# Sheet1.net
KiCad netlist of a schematic drawn in Altium Designer
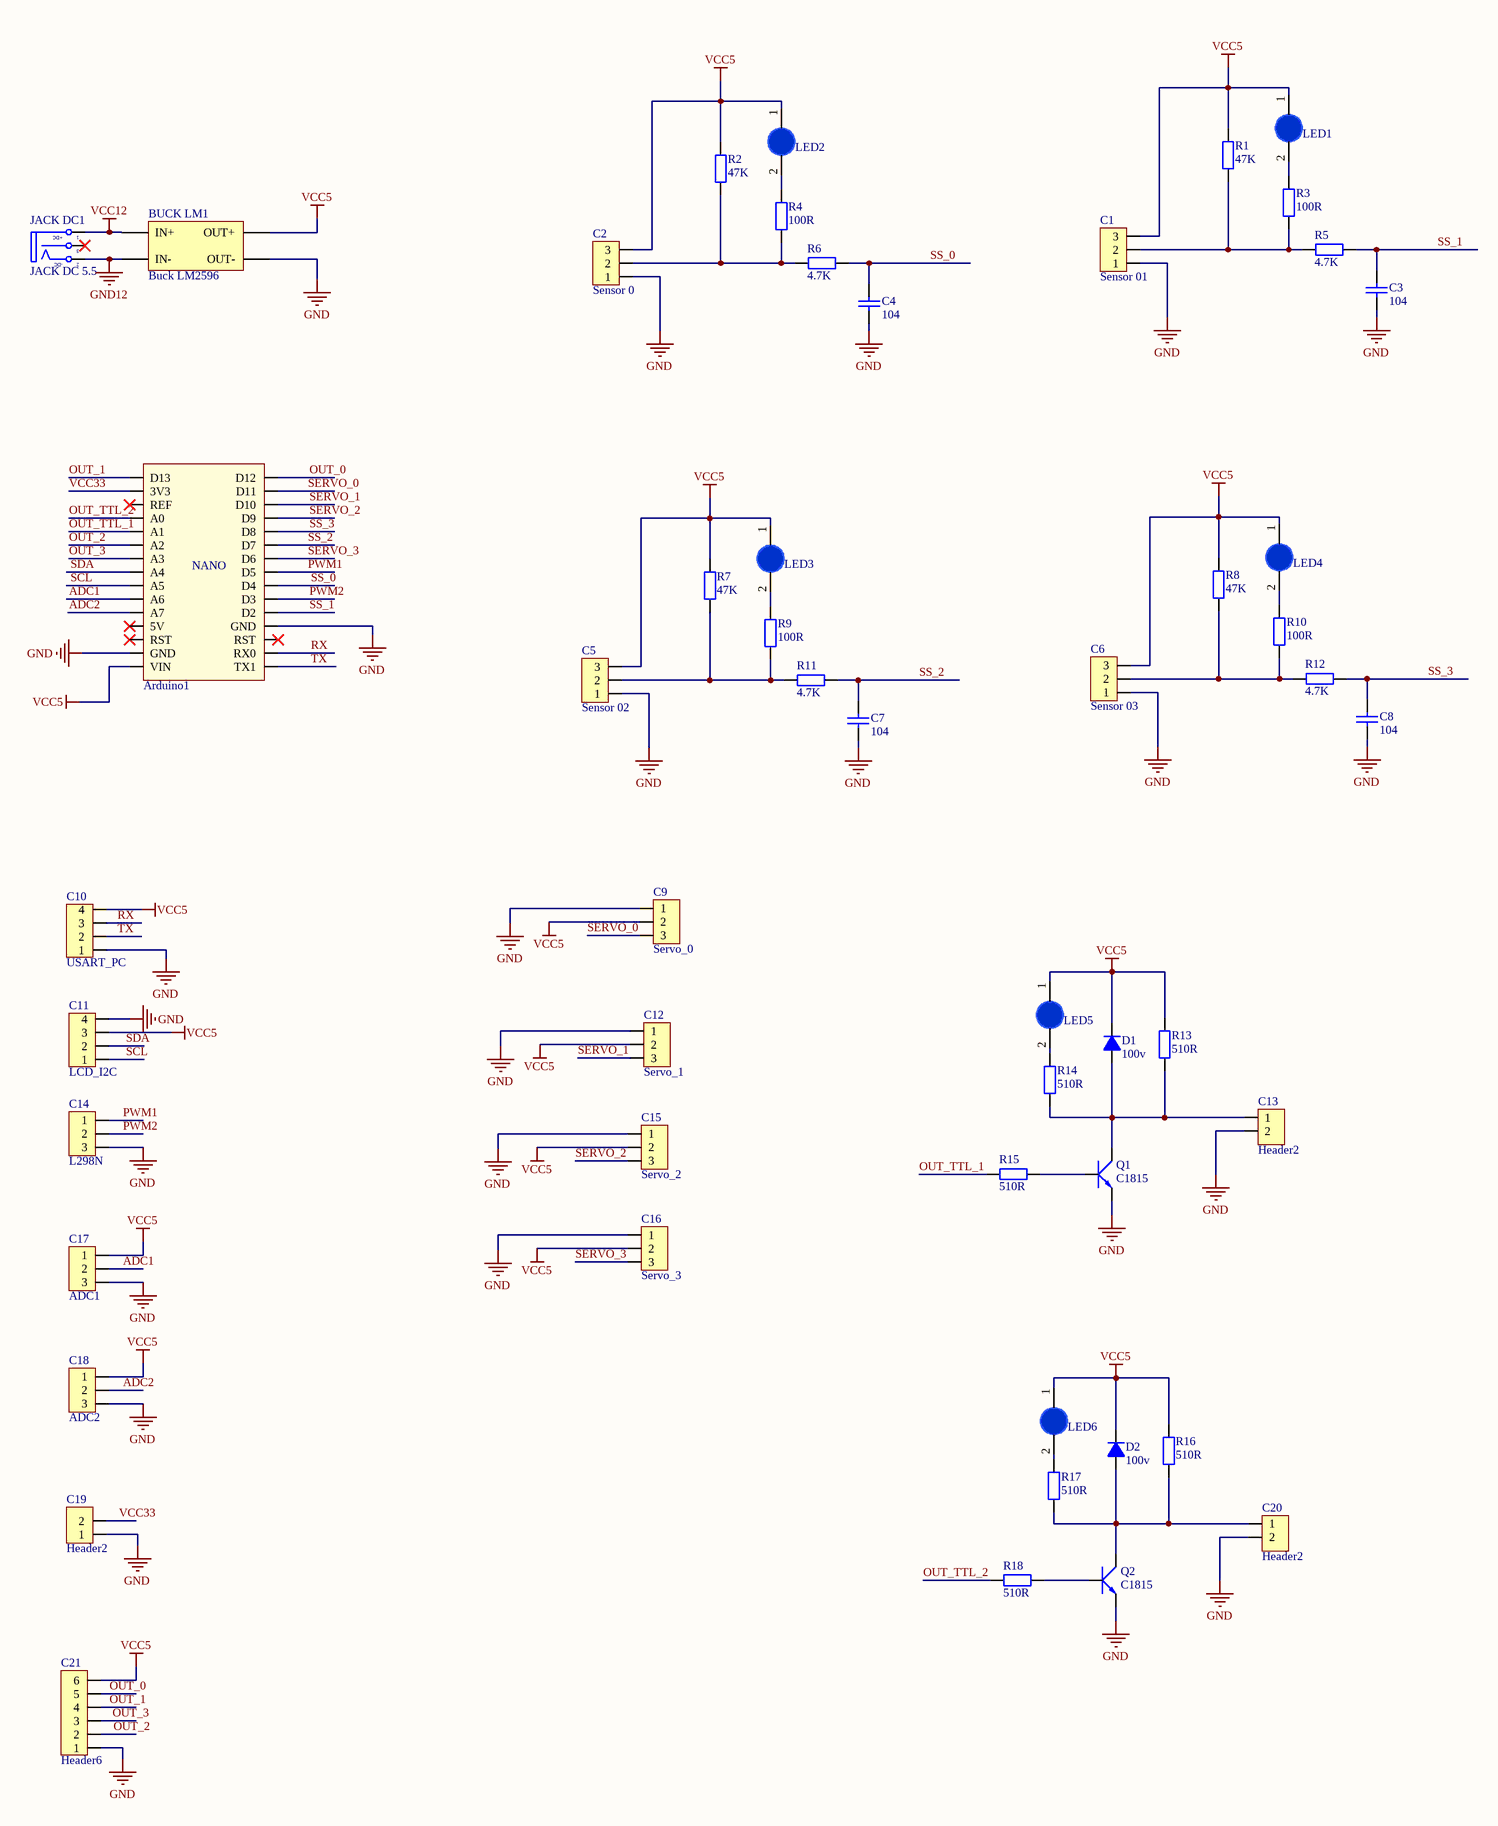
[diagram p0: Sheet1.SchDoc]

(export (version "E")
  (design (tool "Eeschema 10.0.6"))
  (components
    (comp (ref "Arduino1")
      (value "Arduino Nano")
      (footprint "Arduino Nano")
      (description "Arduino NANO")
      (libsource (lib "myLib_v1") (part "Arduino Nano"))
    )
    (comp (ref "BUCK LM1")
      (value "Buck LM2596")
      (footprint "BUCK LM2596")
      (libsource (lib "myLib_v1") (part "Buck LM2596"))
    )
    (comp (ref "C1")
      (value "Sensor 01")
      (footprint "Header3")
      (description "Header IDC, 3 x 1 Pin Vertical 2.54mm Pitch (Non-Boxed, Male)")
      (fields
        (field (name "MANUFACTURER") "Würth Elektronik eiSos GmbH")
        (field (name "PARTNO") "613002143121")
        (field (name "CREATED BY") "Karrer Zheng")
      )
      (libsource (lib "") (part "Header3_1"))
    )
    (comp (ref "C2")
      (value "Sensor 0")
      (footprint "Header3")
      (description "Header IDC, 3 x 1 Pin Vertical 2.54mm Pitch (Non-Boxed, Male)")
      (fields
        (field (name "MANUFACTURER") "Würth Elektronik eiSos GmbH")
        (field (name "PARTNO") "613002143121")
        (field (name "CREATED BY") "Karrer Zheng")
      )
      (libsource (lib "") (part "Header3_1"))
    )
    (comp (ref "C3")
      (value "104")
      (footprint "tu gom")
      (description "Cắm")
      (libsource (lib "Altium_Lib_by_KhueNguyenCreator") (part "Tu gom 104 50V"))
    )
    (comp (ref "C4")
      (value "104")
      (footprint "tu gom")
      (description "Cắm")
      (libsource (lib "Altium_Lib_by_KhueNguyenCreator") (part "Tu gom 104 50V"))
    )
    (comp (ref "C5")
      (value "Sensor 02")
      (footprint "Header3")
      (description "Header IDC, 3 x 1 Pin Vertical 2.54mm Pitch (Non-Boxed, Male)")
      (fields
        (field (name "MANUFACTURER") "Würth Elektronik eiSos GmbH")
        (field (name "PARTNO") "613002143121")
        (field (name "CREATED BY") "Karrer Zheng")
      )
      (libsource (lib "") (part "Header3_1"))
    )
    (comp (ref "C6")
      (value "Sensor 03")
      (footprint "Header3")
      (description "Header IDC, 3 x 1 Pin Vertical 2.54mm Pitch (Non-Boxed, Male)")
      (fields
        (field (name "MANUFACTURER") "Würth Elektronik eiSos GmbH")
        (field (name "PARTNO") "613002143121")
        (field (name "CREATED BY") "Karrer Zheng")
      )
      (libsource (lib "") (part "Header3_1"))
    )
    (comp (ref "C7")
      (value "104")
      (footprint "tu gom")
      (description "Cắm")
      (libsource (lib "Altium_Lib_by_KhueNguyenCreator") (part "Tu gom 104 50V"))
    )
    (comp (ref "C8")
      (value "104")
      (footprint "tu gom")
      (description "Cắm")
      (libsource (lib "Altium_Lib_by_KhueNguyenCreator") (part "Tu gom 104 50V"))
    )
    (comp (ref "C9")
      (value "Servo_0")
      (footprint "Header3")
      (description "Header IDC, 3 x 1 Pin Vertical 2.54mm Pitch (Non-Boxed, Male)")
      (fields
        (field (name "MANUFACTURER") "Würth Elektronik eiSos GmbH")
        (field (name "PARTNO") "613002143121")
        (field (name "CREATED BY") "Karrer Zheng")
      )
      (libsource (lib "") (part "Header3_2"))
    )
    (comp (ref "C10")
      (value "USART_PC")
      (footprint "Header4")
      (description "Header IDC, 4 x 1 Pin Vertical 2.54mm Pitch (Non-Boxed, Male)")
      (fields
        (field (name "MANUFACTURER") "Würth Elektronik eiSos GmbH")
        (field (name "PARTNO") "613002143121")
        (field (name "CREATED BY") "Karrer Zheng")
      )
      (libsource (lib "myLib_v1") (part "Header4"))
    )
    (comp (ref "C11")
      (value "LCD_I2C")
      (footprint "Header4")
      (description "Header IDC, 4 x 1 Pin Vertical 2.54mm Pitch (Non-Boxed, Male)")
      (fields
        (field (name "MANUFACTURER") "Würth Elektronik eiSos GmbH")
        (field (name "PARTNO") "613002143121")
        (field (name "CREATED BY") "Karrer Zheng")
      )
      (libsource (lib "myLib_v1") (part "Header4"))
    )
    (comp (ref "C12")
      (value "Servo_1")
      (footprint "Header3")
      (description "Header IDC, 3 x 1 Pin Vertical 2.54mm Pitch (Non-Boxed, Male)")
      (fields
        (field (name "MANUFACTURER") "Würth Elektronik eiSos GmbH")
        (field (name "PARTNO") "613002143121")
        (field (name "CREATED BY") "Karrer Zheng")
      )
      (libsource (lib "") (part "Header3_2"))
    )
    (comp (ref "C13")
      (value "Header2")
      (footprint "Header2")
      (description "Header IDC, 2 x 1 Pin Vertical 2.54mm Pitch (Non-Boxed, Male)")
      (fields
        (field (name "MANUFACTURER") "Würth Elektronik eiSos GmbH")
        (field (name "PARTNO") "613002143121")
        (field (name "CREATED BY") "Karrer Zheng")
      )
      (libsource (lib "myLib_v1") (part "Header2"))
    )
    (comp (ref "C14")
      (value "L298N")
      (footprint "Header3")
      (description "Header IDC, 3 x 1 Pin Vertical 2.54mm Pitch (Non-Boxed, Male)")
      (fields
        (field (name "MANUFACTURER") "Würth Elektronik eiSos GmbH")
        (field (name "PARTNO") "613002143121")
        (field (name "CREATED BY") "Karrer Zheng")
      )
      (libsource (lib "myLib_v1") (part "Header3"))
    )
    (comp (ref "C15")
      (value "Servo_2")
      (footprint "Header3")
      (description "Header IDC, 3 x 1 Pin Vertical 2.54mm Pitch (Non-Boxed, Male)")
      (fields
        (field (name "MANUFACTURER") "Würth Elektronik eiSos GmbH")
        (field (name "PARTNO") "613002143121")
        (field (name "CREATED BY") "Karrer Zheng")
      )
      (libsource (lib "") (part "Header3_2"))
    )
    (comp (ref "C16")
      (value "Servo_3")
      (footprint "Header3")
      (description "Header IDC, 3 x 1 Pin Vertical 2.54mm Pitch (Non-Boxed, Male)")
      (fields
        (field (name "MANUFACTURER") "Würth Elektronik eiSos GmbH")
        (field (name "PARTNO") "613002143121")
        (field (name "CREATED BY") "Karrer Zheng")
      )
      (libsource (lib "") (part "Header3_2"))
    )
    (comp (ref "C17")
      (value "ADC1")
      (footprint "Header3")
      (description "Header IDC, 3 x 1 Pin Vertical 2.54mm Pitch (Non-Boxed, Male)")
      (fields
        (field (name "MANUFACTURER") "Würth Elektronik eiSos GmbH")
        (field (name "PARTNO") "613002143121")
        (field (name "CREATED BY") "Karrer Zheng")
      )
      (libsource (lib "myLib_v1") (part "Header3"))
    )
    (comp (ref "C18")
      (value "ADC2")
      (footprint "Header3")
      (description "Header IDC, 3 x 1 Pin Vertical 2.54mm Pitch (Non-Boxed, Male)")
      (fields
        (field (name "MANUFACTURER") "Würth Elektronik eiSos GmbH")
        (field (name "PARTNO") "613002143121")
        (field (name "CREATED BY") "Karrer Zheng")
      )
      (libsource (lib "myLib_v1") (part "Header3"))
    )
    (comp (ref "C19")
      (value "Header2")
      (footprint "Header2")
      (description "Header IDC, 2 x 1 Pin Vertical 2.54mm Pitch (Non-Boxed, Male)")
      (fields
        (field (name "MANUFACTURER") "Würth Elektronik eiSos GmbH")
        (field (name "PARTNO") "613002143121")
        (field (name "CREATED BY") "Karrer Zheng")
      )
      (libsource (lib "") (part "Header2_1"))
    )
    (comp (ref "C20")
      (value "Header2")
      (footprint "Header2")
      (description "Header IDC, 2 x 1 Pin Vertical 2.54mm Pitch (Non-Boxed, Male)")
      (fields
        (field (name "MANUFACTURER") "Würth Elektronik eiSos GmbH")
        (field (name "PARTNO") "613002143121")
        (field (name "CREATED BY") "Karrer Zheng")
      )
      (libsource (lib "myLib_v1") (part "Header2"))
    )
    (comp (ref "C21")
      (value "Header6")
      (footprint "Header6")
      (description "Header IDC, 6 x 1 Pin Vertical 2.54mm Pitch (Non-Boxed, Male)")
      (fields
        (field (name "MANUFACTURER") "Würth Elektronik eiSos GmbH")
        (field (name "PARTNO") "613002143121")
        (field (name "CREATED BY") "Karrer Zheng")
      )
      (libsource (lib "myLib_v1") (part "Header6"))
    )
    (comp (ref "D1")
      (value "100v")
      (footprint "DIODE 0.5A")
      (description "Cắm")
      (libsource (lib "Altium_Lib_by_KhueNguyenCreator") (part "Diode 1N4148"))
    )
    (comp (ref "D2")
      (value "100v")
      (footprint "DIODE 0.5A")
      (description "Cắm")
      (libsource (lib "Altium_Lib_by_KhueNguyenCreator") (part "Diode 1N4148"))
    )
    (comp (ref "JACK DC1")
      (value "JACK DC 5.5")
      (footprint "JACK DC 5.5")
      (libsource (lib "Altium_Lib_by_KhueNguyenCreator") (part "JACK DC 5.5"))
    )
    (comp (ref "LED1")
      (value "LED 3mm")
      (footprint "LED-3MM-BLUE")
      (description "Cắm")
      (libsource (lib "myLib_v1") (part "LED 3mm Xanh Duong"))
    )
    (comp (ref "LED2")
      (value "LED 3mm")
      (footprint "LED-3MM-BLUE")
      (description "Cắm")
      (libsource (lib "myLib_v1") (part "LED 3mm Xanh Duong"))
    )
    (comp (ref "LED3")
      (value "LED 3mm")
      (footprint "LED-3MM-BLUE")
      (description "Cắm")
      (libsource (lib "myLib_v1") (part "LED 3mm Xanh Duong"))
    )
    (comp (ref "LED4")
      (value "LED 3mm")
      (footprint "LED-3MM-BLUE")
      (description "Cắm")
      (libsource (lib "myLib_v1") (part "LED 3mm Xanh Duong"))
    )
    (comp (ref "LED5")
      (value "LED 3mm")
      (footprint "LED-3MM-BLUE")
      (description "Cắm")
      (libsource (lib "myLib_v1") (part "LED 3mm Xanh Duong"))
    )
    (comp (ref "LED6")
      (value "LED 3mm")
      (footprint "LED-3MM-BLUE")
      (description "Cắm")
      (libsource (lib "myLib_v1") (part "LED 3mm Xanh Duong"))
    )
    (comp (ref "Q1")
      (value "C1815")
      (footprint "C1815_cam")
      (description "NPN 600mW, ECB")
      (libsource (lib "myLib_v1") (part "C1815"))
    )
    (comp (ref "Q2")
      (value "C1815")
      (footprint "C1815_cam")
      (description "NPN 600mW, ECB")
      (libsource (lib "myLib_v1") (part "C1815"))
    )
    (comp (ref "R1")
      (value "47K")
      (footprint "R1/4W")
      (description "Resistor 1/4W")
      (libsource (lib "myLib_v1") (part "R1/4W"))
    )
    (comp (ref "R2")
      (value "47K")
      (footprint "R1/4W")
      (description "Resistor 1/4W")
      (libsource (lib "myLib_v1") (part "R1/4W"))
    )
    (comp (ref "R3")
      (value "100R")
      (footprint "R1/4W")
      (description "Resistor 1/4W")
      (libsource (lib "myLib_v1") (part "R1/4W"))
    )
    (comp (ref "R4")
      (value "100R")
      (footprint "R1/4W")
      (description "Resistor 1/4W")
      (libsource (lib "myLib_v1") (part "R1/4W"))
    )
    (comp (ref "R5")
      (value "4.7K")
      (footprint "R1/4W")
      (description "Resistor 1/4W")
      (libsource (lib "myLib_v1") (part "R1/4W"))
    )
    (comp (ref "R6")
      (value "4.7K")
      (footprint "R1/4W")
      (description "Resistor 1/4W")
      (libsource (lib "myLib_v1") (part "R1/4W"))
    )
    (comp (ref "R7")
      (value "47K")
      (footprint "R1/4W")
      (description "Resistor 1/4W")
      (libsource (lib "myLib_v1") (part "R1/4W"))
    )
    (comp (ref "R8")
      (value "47K")
      (footprint "R1/4W")
      (description "Resistor 1/4W")
      (libsource (lib "myLib_v1") (part "R1/4W"))
    )
    (comp (ref "R9")
      (value "100R")
      (footprint "R1/4W")
      (description "Resistor 1/4W")
      (libsource (lib "myLib_v1") (part "R1/4W"))
    )
    (comp (ref "R10")
      (value "100R")
      (footprint "R1/4W")
      (description "Resistor 1/4W")
      (libsource (lib "myLib_v1") (part "R1/4W"))
    )
    (comp (ref "R11")
      (value "4.7K")
      (footprint "R1/4W")
      (description "Resistor 1/4W")
      (libsource (lib "myLib_v1") (part "R1/4W"))
    )
    (comp (ref "R12")
      (value "4.7K")
      (footprint "R1/4W")
      (description "Resistor 1/4W")
      (libsource (lib "myLib_v1") (part "R1/4W"))
    )
    (comp (ref "R13")
      (value "510R")
      (footprint "R1/4W")
      (description "Resistor 1/4W")
      (libsource (lib "myLib_v1") (part "R1/4W"))
    )
    (comp (ref "R14")
      (value "510R")
      (footprint "R1/4W")
      (description "Resistor 1/4W")
      (libsource (lib "myLib_v1") (part "R1/4W"))
    )
    (comp (ref "R15")
      (value "510R")
      (footprint "R1/4W")
      (description "Resistor 1/4W")
      (libsource (lib "myLib_v1") (part "R1/4W"))
    )
    (comp (ref "R16")
      (value "510R")
      (footprint "R1/4W")
      (description "Resistor 1/4W")
      (libsource (lib "myLib_v1") (part "R1/4W"))
    )
    (comp (ref "R17")
      (value "510R")
      (footprint "R1/4W")
      (description "Resistor 1/4W")
      (libsource (lib "myLib_v1") (part "R1/4W"))
    )
    (comp (ref "R18")
      (value "510R")
      (footprint "R1/4W")
      (description "Resistor 1/4W")
      (libsource (lib "myLib_v1") (part "R1/4W"))
    )
  )
  (nets
    (net (code "1") (name "/ADC1") (class "Default")
      (node (ref "Arduino1") (pin "A6") (pinfunction "A6_A6") (pintype "passive"))
      (node (ref "C17") (pin "2") (pinfunction "2_2") (pintype "passive"))
    )
    (net (code "2") (name "/ADC2") (class "Default")
      (node (ref "Arduino1") (pin "A7") (pinfunction "A7_A7") (pintype "passive"))
      (node (ref "C18") (pin "2") (pinfunction "2_2") (pintype "passive"))
    )
    (net (code "3") (name "/OUT_0") (class "Default")
      (node (ref "Arduino1") (pin "D12") (pinfunction "D12_D12") (pintype "passive"))
      (node (ref "C21") (pin "5") (pinfunction "5_5") (pintype "passive"))
    )
    (net (code "4") (name "/OUT_1") (class "Default")
      (node (ref "Arduino1") (pin "D13") (pinfunction "D13_D13") (pintype "passive"))
      (node (ref "C21") (pin "4") (pinfunction "4_4") (pintype "passive"))
    )
    (net (code "5") (name "/OUT_2") (class "Default")
      (node (ref "Arduino1") (pin "A2") (pinfunction "A2_A2") (pintype "passive"))
      (node (ref "C21") (pin "2") (pinfunction "2_2") (pintype "passive"))
    )
    (net (code "6") (name "/OUT_3") (class "Default")
      (node (ref "Arduino1") (pin "A3") (pinfunction "A3_A3") (pintype "passive"))
      (node (ref "C21") (pin "3") (pinfunction "3_3") (pintype "passive"))
    )
    (net (code "7") (name "/OUT_TTL_1") (class "Default")
      (node (ref "Arduino1") (pin "A1") (pinfunction "A1_A1") (pintype "passive"))
      (node (ref "R15") (pin "1") (pinfunction "1_1") (pintype "passive"))
    )
    (net (code "8") (name "/OUT_TTL_2") (class "Default")
      (node (ref "Arduino1") (pin "A0") (pinfunction "A0_A0") (pintype "passive"))
      (node (ref "R18") (pin "1") (pinfunction "1_1") (pintype "passive"))
    )
    (net (code "9") (name "/PWM1") (class "Default")
      (node (ref "Arduino1") (pin "D5") (pinfunction "D5_D5") (pintype "passive"))
      (node (ref "C14") (pin "1") (pinfunction "1_1") (pintype "passive"))
    )
    (net (code "10") (name "/PWM2") (class "Default")
      (node (ref "Arduino1") (pin "D3") (pinfunction "D3_D3") (pintype "passive"))
      (node (ref "C14") (pin "2") (pinfunction "2_2") (pintype "passive"))
    )
    (net (code "11") (name "/RX") (class "Default")
      (node (ref "Arduino1") (pin "RX0") (pinfunction "RX0_RX0") (pintype "passive"))
      (node (ref "C10") (pin "3") (pinfunction "3_3") (pintype "passive"))
    )
    (net (code "12") (name "/SCL") (class "Default")
      (node (ref "Arduino1") (pin "A5") (pinfunction "A5_A5") (pintype "passive"))
      (node (ref "C11") (pin "1") (pinfunction "1_1") (pintype "passive"))
    )
    (net (code "13") (name "/SDA") (class "Default")
      (node (ref "Arduino1") (pin "A4") (pinfunction "A4_A4") (pintype "passive"))
      (node (ref "C11") (pin "2") (pinfunction "2_2") (pintype "passive"))
    )
    (net (code "14") (name "/SERVO_0") (class "Default")
      (node (ref "Arduino1") (pin "D11") (pinfunction "D11_D11") (pintype "passive"))
      (node (ref "C9") (pin "3") (pinfunction "3_3") (pintype "passive"))
    )
    (net (code "15") (name "/SERVO_1") (class "Default")
      (node (ref "Arduino1") (pin "D10") (pinfunction "D10_D10") (pintype "passive"))
      (node (ref "C12") (pin "3") (pinfunction "3_3") (pintype "passive"))
    )
    (net (code "16") (name "/SERVO_2") (class "Default")
      (node (ref "Arduino1") (pin "D9") (pinfunction "D9_D9") (pintype "passive"))
      (node (ref "C15") (pin "3") (pinfunction "3_3") (pintype "passive"))
    )
    (net (code "17") (name "/SERVO_3") (class "Default")
      (node (ref "Arduino1") (pin "D6") (pinfunction "D6_D6") (pintype "passive"))
      (node (ref "C16") (pin "3") (pinfunction "3_3") (pintype "passive"))
    )
    (net (code "18") (name "/SS_0") (class "Default")
      (node (ref "Arduino1") (pin "D4") (pinfunction "D4_D4") (pintype "passive"))
      (node (ref "C4") (pin "1") (pinfunction "1_1") (pintype "passive"))
      (node (ref "R6") (pin "1") (pinfunction "1_1") (pintype "passive"))
    )
    (net (code "19") (name "/SS_1") (class "Default")
      (node (ref "Arduino1") (pin "D2") (pinfunction "D2_D2") (pintype "passive"))
      (node (ref "C3") (pin "1") (pinfunction "1_1") (pintype "passive"))
      (node (ref "R5") (pin "1") (pinfunction "1_1") (pintype "passive"))
    )
    (net (code "20") (name "/SS_2") (class "Default")
      (node (ref "Arduino1") (pin "D7") (pinfunction "D7_D7") (pintype "passive"))
      (node (ref "C7") (pin "1") (pinfunction "1_1") (pintype "passive"))
      (node (ref "R11") (pin "1") (pinfunction "1_1") (pintype "passive"))
    )
    (net (code "21") (name "/SS_3") (class "Default")
      (node (ref "Arduino1") (pin "D8") (pinfunction "D8_D8") (pintype "passive"))
      (node (ref "C8") (pin "1") (pinfunction "1_1") (pintype "passive"))
      (node (ref "R12") (pin "1") (pinfunction "1_1") (pintype "passive"))
    )
    (net (code "22") (name "/TX") (class "Default")
      (node (ref "Arduino1") (pin "TX1") (pinfunction "TX1_TX1") (pintype "passive"))
      (node (ref "C10") (pin "2") (pinfunction "2_2") (pintype "passive"))
    )
    (net (code "23") (name "/VCC33") (class "Default")
      (node (ref "Arduino1") (pin "3V3") (pinfunction "3V3_3V3") (pintype "passive"))
      (node (ref "C19") (pin "2") (pinfunction "2_2") (pintype "passive"))
    )
    (net (code "24") (name "GND") (class "Default")
      (node (ref "Arduino1") (pin "GND") (pinfunction "GND_GND") (pintype "passive"))
      (node (ref "BUCK LM1") (pin "3") (pinfunction "OUT-_3") (pintype "passive"))
      (node (ref "C1") (pin "1") (pinfunction "1_1") (pintype "passive"))
      (node (ref "C10") (pin "1") (pinfunction "1_1") (pintype "passive"))
      (node (ref "C11") (pin "4") (pinfunction "4_4") (pintype "passive"))
      (node (ref "C12") (pin "1") (pinfunction "1_1") (pintype "passive"))
      (node (ref "C13") (pin "2") (pinfunction "2_2") (pintype "passive"))
      (node (ref "C14") (pin "3") (pinfunction "3_3") (pintype "passive"))
      (node (ref "C15") (pin "1") (pinfunction "1_1") (pintype "passive"))
      (node (ref "C16") (pin "1") (pinfunction "1_1") (pintype "passive"))
      (node (ref "C17") (pin "3") (pinfunction "3_3") (pintype "passive"))
      (node (ref "C18") (pin "3") (pinfunction "3_3") (pintype "passive"))
      (node (ref "C19") (pin "1") (pinfunction "1_1") (pintype "passive"))
      (node (ref "C2") (pin "1") (pinfunction "1_1") (pintype "passive"))
      (node (ref "C20") (pin "2") (pinfunction "2_2") (pintype "passive"))
      (node (ref "C21") (pin "1") (pinfunction "1_1") (pintype "passive"))
      (node (ref "C3") (pin "2") (pinfunction "2_2") (pintype "passive"))
      (node (ref "C4") (pin "2") (pinfunction "2_2") (pintype "passive"))
      (node (ref "C5") (pin "1") (pinfunction "1_1") (pintype "passive"))
      (node (ref "C6") (pin "1") (pinfunction "1_1") (pintype "passive"))
      (node (ref "C7") (pin "2") (pinfunction "2_2") (pintype "passive"))
      (node (ref "C8") (pin "2") (pinfunction "2_2") (pintype "passive"))
      (node (ref "C9") (pin "1") (pinfunction "1_1") (pintype "passive"))
      (node (ref "Q1") (pin "1") (pinfunction "E_1") (pintype "passive"))
      (node (ref "Q2") (pin "1") (pinfunction "E_1") (pintype "passive"))
    )
    (net (code "25") (name "GND12") (class "Default")
      (node (ref "BUCK LM1") (pin "2") (pinfunction "IN-_2") (pintype "passive"))
      (node (ref "JACK DC1") (pin "2") (pinfunction "TN_2") (pintype "passive"))
    )
    (net (code "26") (name "Net-(C1-Pad2)") (class "Default")
      (node (ref "C1") (pin "2") (pinfunction "2_2") (pintype "passive"))
      (node (ref "R1") (pin "1") (pinfunction "1_1") (pintype "passive"))
      (node (ref "R3") (pin "1") (pinfunction "1_1") (pintype "passive"))
      (node (ref "R5") (pin "2") (pinfunction "2_2") (pintype "passive"))
    )
    (net (code "27") (name "Net-(C2-Pad2)") (class "Default")
      (node (ref "C2") (pin "2") (pinfunction "2_2") (pintype "passive"))
      (node (ref "R2") (pin "1") (pinfunction "1_1") (pintype "passive"))
      (node (ref "R4") (pin "1") (pinfunction "1_1") (pintype "passive"))
      (node (ref "R6") (pin "2") (pinfunction "2_2") (pintype "passive"))
    )
    (net (code "28") (name "Net-(C5-Pad2)") (class "Default")
      (node (ref "C5") (pin "2") (pinfunction "2_2") (pintype "passive"))
      (node (ref "R11") (pin "2") (pinfunction "2_2") (pintype "passive"))
      (node (ref "R7") (pin "1") (pinfunction "1_1") (pintype "passive"))
      (node (ref "R9") (pin "1") (pinfunction "1_1") (pintype "passive"))
    )
    (net (code "29") (name "Net-(C6-Pad2)") (class "Default")
      (node (ref "C6") (pin "2") (pinfunction "2_2") (pintype "passive"))
      (node (ref "R10") (pin "1") (pinfunction "1_1") (pintype "passive"))
      (node (ref "R12") (pin "2") (pinfunction "2_2") (pintype "passive"))
      (node (ref "R8") (pin "1") (pinfunction "1_1") (pintype "passive"))
    )
    (net (code "30") (name "Net-(D1-A)") (class "Default")
      (node (ref "C13") (pin "1") (pinfunction "1_1") (pintype "passive"))
      (node (ref "D1") (pin "1") (pinfunction "A_1") (pintype "passive"))
      (node (ref "Q1") (pin "2") (pinfunction "C_2") (pintype "passive"))
      (node (ref "R13") (pin "2") (pinfunction "2_2") (pintype "passive"))
      (node (ref "R14") (pin "2") (pinfunction "2_2") (pintype "passive"))
    )
    (net (code "31") (name "Net-(D2-A)") (class "Default")
      (node (ref "C20") (pin "1") (pinfunction "1_1") (pintype "passive"))
      (node (ref "D2") (pin "1") (pinfunction "A_1") (pintype "passive"))
      (node (ref "Q2") (pin "2") (pinfunction "C_2") (pintype "passive"))
      (node (ref "R16") (pin "2") (pinfunction "2_2") (pintype "passive"))
      (node (ref "R17") (pin "2") (pinfunction "2_2") (pintype "passive"))
    )
    (net (code "32") (name "Net-(LED1-K)") (class "Default")
      (node (ref "LED1") (pin "2") (pinfunction "K_2") (pintype "passive"))
      (node (ref "R3") (pin "2") (pinfunction "2_2") (pintype "passive"))
    )
    (net (code "33") (name "Net-(LED2-K)") (class "Default")
      (node (ref "LED2") (pin "2") (pinfunction "K_2") (pintype "passive"))
      (node (ref "R4") (pin "2") (pinfunction "2_2") (pintype "passive"))
    )
    (net (code "34") (name "Net-(LED3-K)") (class "Default")
      (node (ref "LED3") (pin "2") (pinfunction "K_2") (pintype "passive"))
      (node (ref "R9") (pin "2") (pinfunction "2_2") (pintype "passive"))
    )
    (net (code "35") (name "Net-(LED4-K)") (class "Default")
      (node (ref "LED4") (pin "2") (pinfunction "K_2") (pintype "passive"))
      (node (ref "R10") (pin "2") (pinfunction "2_2") (pintype "passive"))
    )
    (net (code "36") (name "Net-(LED5-K)") (class "Default")
      (node (ref "LED5") (pin "2") (pinfunction "K_2") (pintype "passive"))
      (node (ref "R14") (pin "1") (pinfunction "1_1") (pintype "passive"))
    )
    (net (code "37") (name "Net-(LED6-K)") (class "Default")
      (node (ref "LED6") (pin "2") (pinfunction "K_2") (pintype "passive"))
      (node (ref "R17") (pin "1") (pinfunction "1_1") (pintype "passive"))
    )
    (net (code "38") (name "Net-(Q1-B)") (class "Default")
      (node (ref "Q1") (pin "3") (pinfunction "B_3") (pintype "passive"))
      (node (ref "R15") (pin "2") (pinfunction "2_2") (pintype "passive"))
    )
    (net (code "39") (name "Net-(Q2-B)") (class "Default")
      (node (ref "Q2") (pin "3") (pinfunction "B_3") (pintype "passive"))
      (node (ref "R18") (pin "2") (pinfunction "2_2") (pintype "passive"))
    )
    (net (code "40") (name "VCC5") (class "Default")
      (node (ref "Arduino1") (pin "VIN") (pinfunction "VIN_VIN") (pintype "passive"))
      (node (ref "BUCK LM1") (pin "4") (pinfunction "OUT+_4") (pintype "passive"))
      (node (ref "C1") (pin "3") (pinfunction "3_3") (pintype "passive"))
      (node (ref "C10") (pin "4") (pinfunction "4_4") (pintype "passive"))
      (node (ref "C11") (pin "3") (pinfunction "3_3") (pintype "passive"))
      (node (ref "C12") (pin "2") (pinfunction "2_2") (pintype "passive"))
      (node (ref "C15") (pin "2") (pinfunction "2_2") (pintype "passive"))
      (node (ref "C16") (pin "2") (pinfunction "2_2") (pintype "passive"))
      (node (ref "C17") (pin "1") (pinfunction "1_1") (pintype "passive"))
      (node (ref "C18") (pin "1") (pinfunction "1_1") (pintype "passive"))
      (node (ref "C2") (pin "3") (pinfunction "3_3") (pintype "passive"))
      (node (ref "C21") (pin "6") (pinfunction "6_6") (pintype "passive"))
      (node (ref "C5") (pin "3") (pinfunction "3_3") (pintype "passive"))
      (node (ref "C6") (pin "3") (pinfunction "3_3") (pintype "passive"))
      (node (ref "C9") (pin "2") (pinfunction "2_2") (pintype "passive"))
      (node (ref "D1") (pin "2") (pinfunction "K_2") (pintype "passive"))
      (node (ref "D2") (pin "2") (pinfunction "K_2") (pintype "passive"))
      (node (ref "LED1") (pin "1") (pinfunction "A_1") (pintype "passive"))
      (node (ref "LED2") (pin "1") (pinfunction "A_1") (pintype "passive"))
      (node (ref "LED3") (pin "1") (pinfunction "A_1") (pintype "passive"))
      (node (ref "LED4") (pin "1") (pinfunction "A_1") (pintype "passive"))
      (node (ref "LED5") (pin "1") (pinfunction "A_1") (pintype "passive"))
      (node (ref "LED6") (pin "1") (pinfunction "A_1") (pintype "passive"))
      (node (ref "R1") (pin "2") (pinfunction "2_2") (pintype "passive"))
      (node (ref "R13") (pin "1") (pinfunction "1_1") (pintype "passive"))
      (node (ref "R16") (pin "1") (pinfunction "1_1") (pintype "passive"))
      (node (ref "R2") (pin "2") (pinfunction "2_2") (pintype "passive"))
      (node (ref "R7") (pin "2") (pinfunction "2_2") (pintype "passive"))
      (node (ref "R8") (pin "2") (pinfunction "2_2") (pintype "passive"))
    )
    (net (code "41") (name "VCC12") (class "Default")
      (node (ref "BUCK LM1") (pin "1") (pinfunction "IN+_1") (pintype "passive"))
      (node (ref "JACK DC1") (pin "1") (pinfunction "T_1") (pintype "passive"))
    )
    (net (code "42") (name "unconnected-(Arduino1-Pad5V)") (class "Default")
      (node (ref "Arduino1") (pin "5V") (pinfunction "5V_5V") (pintype "passive+no_connect"))
    )
    (net (code "43") (name "unconnected-(Arduino1-PadREF)") (class "Default")
      (node (ref "Arduino1") (pin "REF") (pinfunction "REF_REF") (pintype "passive+no_connect"))
    )
    (net (code "44") (name "unconnected-(Arduino1-PadRST)") (class "Default")
      (node (ref "Arduino1") (pin "RST") (pinfunction "RST_RST") (pintype "passive+no_connect"))
    )
    (net (code "45") (name "unconnected-(Arduino1-PadRST)_1") (class "Default")
      (node (ref "Arduino1") (pin "RST") (pinfunction "RST_RST") (pintype "passive+no_connect"))
    )
    (net (code "46") (name "unconnected-(JACK DC1-S-Pad3)") (class "Default")
      (node (ref "JACK DC1") (pin "3") (pinfunction "S_3") (pintype "power_in+no_connect"))
    )
  )
)
